# Receivers.net
KiCad netlist of a schematic drawn in Altium Designer
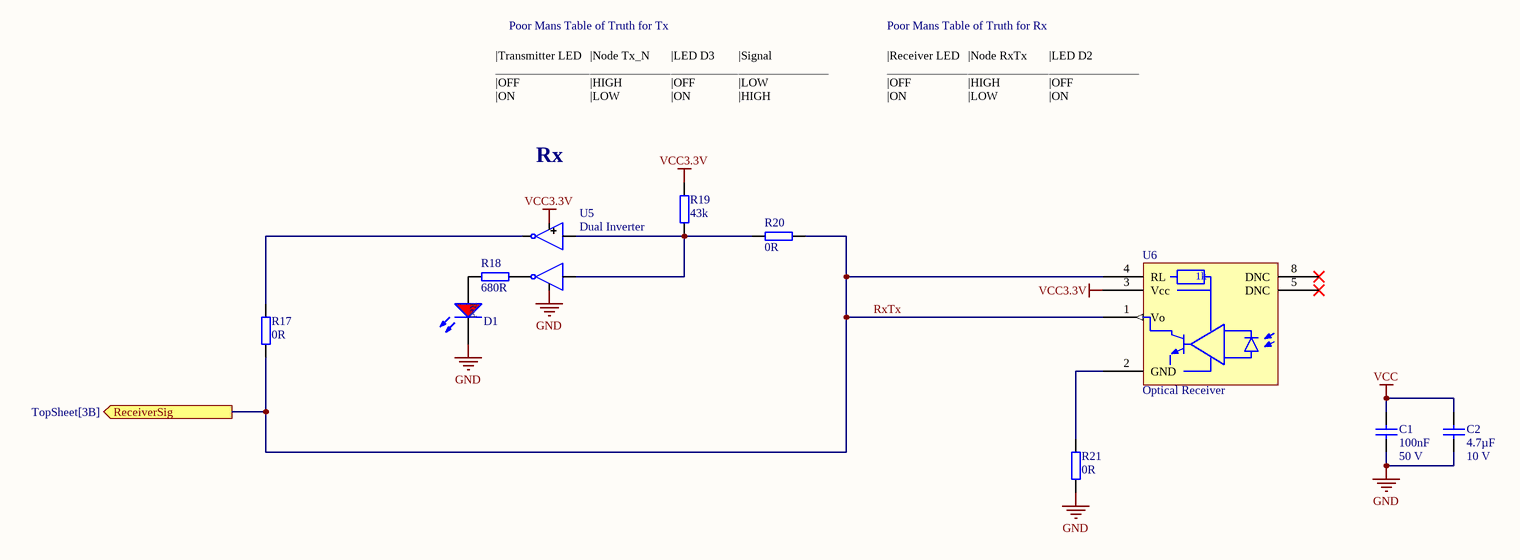
[diagram p0: Receivers.SchDoc]

(export (version "E")
  (design (tool "Eeschema 10.0.6"))
  (components
    (comp (ref "C1")
      (value "100nF")
      (footprint "C_0603(1608)100_L")
      (description "CAP 0603 (1608 Metric) SMD")
      (fields
        (field (name "TOLERANCE") "±5%")
        (field (name "LCSC PART #") "C14663")
        (field (name "RATED VOLTAGE") "50 V")
        (field (name "CREATED") "2018_09_06_AGeiger")
      )
      (libsource (lib "UZOhm_Optical") (part "C_0603"))
    )
    (comp (ref "C2")
      (value "4.7µF")
      (footprint "CAP_2012X06N")
      (description "CAP 0805 (2012 Metric) SMD")
      (fields
        (field (name "TOLERANCE") "±10%")
        (field (name "MF") "Taiyo Yuden")
        (field (name "VOLTAGE") "10 V")
        (field (name "CREATED") "2018_09_06_AGeiger")
      )
      (libsource (lib "UZOhm_Optical") (part "C_0805"))
    )
    (comp (ref "D1")
      (value "150060RS75000")
      (footprint "WL-SMCW_0603")
      (description "WL-SMCW SMD Mono-color Chip LED Waterclear, size 0603, Red, 2 V, 140°")
      (fields
        (field (name "MF") "Wuerth Elektronik")
        (field (name "LCSC PART #") "C2286")
        (field (name "CREATED") "2018_09_06_AGeiger")
      )
      (libsource (lib "UZOhm_Optical") (part "LED_Red_0603"))
    )
    (comp (ref "R17")
      (value "0R")
      (footprint "R_0603_N")
      (description "SMD Resistor 0603")
      (fields
        (field (name "TOLERANCE") "1%")
        (field (name "VOLTAGE") "75V")
        (field (name "CREATED") "2018_09_06_AGeiger")
      )
      (libsource (lib "UZOhm_Optical") (part "R_0603_JLC"))
    )
    (comp (ref "R18")
      (value "680R")
      (footprint "R_0603_N")
      (description "SMD Resistor 0603")
      (fields
        (field (name "TOLERANCE") "1%")
        (field (name "VOLTAGE") "75V")
        (field (name "CREATED") "2018_09_06_AGeiger")
      )
      (libsource (lib "UZOhm_Optical") (part "R_0603"))
    )
    (comp (ref "R19")
      (value "43k")
      (footprint "R_0603_N")
      (description "SMD Resistor 0603")
      (fields
        (field (name "TOLERANCE") "1%")
        (field (name "VOLTAGE") "50V")
        (field (name "CREATED") "2018_09_06_AGeiger")
      )
      (libsource (lib "UZOhm_Optical") (part "R_0603_JLC"))
    )
    (comp (ref "R20")
      (value "0R")
      (footprint "R_0603_N")
      (description "SMD Resistor 0603")
      (fields
        (field (name "TOLERANCE") "1%")
        (field (name "VOLTAGE") "75V")
        (field (name "CREATED") "2018_09_06_AGeiger")
      )
      (libsource (lib "UZOhm_Optical") (part "R_0603_JLC"))
    )
    (comp (ref "R21")
      (value "0R")
      (footprint "R_0603_N")
      (description "SMD Resistor 0603")
      (fields
        (field (name "TOLERANCE") "1%")
        (field (name "VOLTAGE") "75V")
        (field (name "CREATED") "2018_09_06_AGeiger")
      )
      (libsource (lib "UZOhm_Optical") (part "R_0603"))
    )
    (comp (ref "U5")
      (value "Dual Inverter")
      (footprint "SN74LVC2GU04DCKR")
      (description "This dual inverter is designed for 1.65-V to 5.5-V VCC\r\noperation.")
      (fields (field (name "LCSC PART #") "C116660"))
      (libsource (lib "UZOhm_Optical") (part "SN74LVC2GU04DCKR"))
    )
    (comp (ref "U6")
      (value "Optical Receiver")
      (footprint "HFBRx5XX")
      (description "Fibre Optic Receivers, LINK HORIZ 5MBd RC VR RoHS")
      (fields
        (field (name "MF") "Boadcom/Avago")
        (field (name "MPN") "HFBR-2521Z")
        (field (name "CREATED") "2019_04_09_Kreppel")
      )
      (libsource (lib "UZOhm_Optical") (part "HFBR-2528Z"))
    )
  )
  (nets
    (net (code "1") (name "/RxTx") (class "Default")
      (node (ref "R17") (pin "1") (pinfunction "1_1") (pintype "passive"))
      (node (ref "R20") (pin "2") (pinfunction "2_2") (pintype "passive"))
      (node (ref "U6") (pin "1") (pinfunction "Vo_1") (pintype "output"))
      (node (ref "U6") (pin "4") (pinfunction "RL_4") (pintype "passive"))
    )
    (net (code "2") (name "GND") (class "Default")
      (node (ref "C1") (pin "2") (pinfunction "2_2") (pintype "passive"))
      (node (ref "C2") (pin "2") (pinfunction "2_2") (pintype "passive"))
      (node (ref "D1") (pin "1") (pinfunction "K_1") (pintype "passive"))
      (node (ref "R21") (pin "2") (pinfunction "2_2") (pintype "passive"))
      (node (ref "U5") (pin "2") (pinfunction "GND_2") (pintype "passive"))
    )
    (net (code "3") (name "Net-(D1-A)") (class "Default")
      (node (ref "D1") (pin "2") (pinfunction "A_2") (pintype "passive"))
      (node (ref "R18") (pin "2") (pinfunction "2_2") (pintype "passive"))
    )
    (net (code "4") (name "Net-(R17-Pad2)") (class "Default")
      (node (ref "R17") (pin "2") (pinfunction "2_2") (pintype "passive"))
      (node (ref "U5") (pin "6") (pinfunction "OUT2_6") (pintype "passive"))
    )
    (net (code "5") (name "Net-(R18-Pad1)") (class "Default")
      (node (ref "R18") (pin "1") (pinfunction "1_1") (pintype "passive"))
      (node (ref "U5") (pin "4") (pinfunction "OUT2_4") (pintype "passive"))
    )
    (net (code "6") (name "Net-(U5-IN1)") (class "Default")
      (node (ref "R19") (pin "2") (pinfunction "2_2") (pintype "passive"))
      (node (ref "R20") (pin "1") (pinfunction "1_1") (pintype "passive"))
      (node (ref "U5") (pin "1") (pinfunction "IN1_1") (pintype "passive"))
      (node (ref "U5") (pin "3") (pinfunction "IN2_3") (pintype "passive"))
    )
    (net (code "7") (name "Net-(U6-GND)") (class "Default")
      (node (ref "R21") (pin "1") (pinfunction "1_1") (pintype "passive"))
      (node (ref "U6") (pin "2") (pinfunction "GND_2") (pintype "power_in"))
    )
    (net (code "8") (name "VCC") (class "Default")
      (node (ref "C1") (pin "1") (pinfunction "1_1") (pintype "passive"))
      (node (ref "C2") (pin "1") (pinfunction "1_1") (pintype "passive"))
    )
    (net (code "9") (name "VCC3.3V") (class "Default")
      (node (ref "R19") (pin "1") (pinfunction "1_1") (pintype "passive"))
      (node (ref "U5") (pin "5") (pinfunction "VCC_5") (pintype "passive"))
      (node (ref "U6") (pin "3") (pinfunction "Vcc_3") (pintype "power_in"))
    )
    (net (code "10") (name "unconnected-(U6-DNC-Pad5)") (class "Default")
      (node (ref "U6") (pin "5") (pinfunction "DNC_5") (pintype "passive+no_connect"))
    )
    (net (code "11") (name "unconnected-(U6-DNC-Pad8)") (class "Default")
      (node (ref "U6") (pin "8") (pinfunction "DNC_8") (pintype "passive+no_connect"))
    )
  )
)
